# LED.net
KiCad netlist of a schematic drawn in Altium Designer
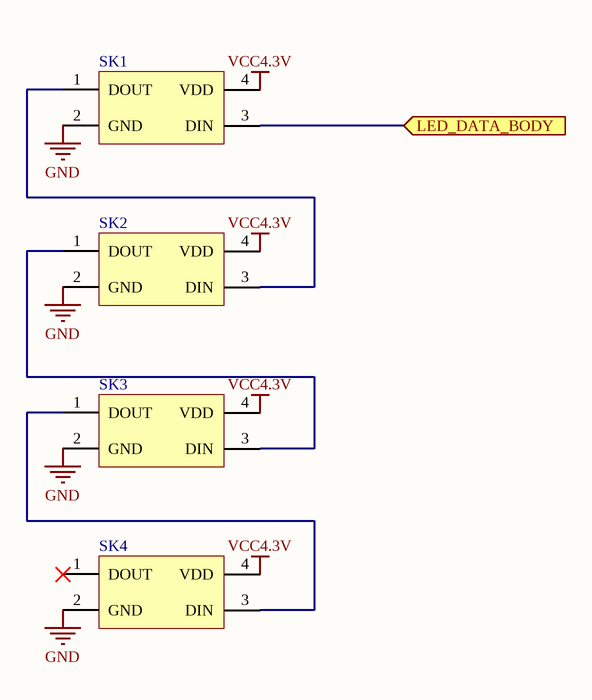
[diagram p0: LED.SchDoc]

(export (version "E")
  (design (tool "Eeschema 10.0.6"))
  (components
    (comp (ref "SK1")
      (value "LED_3535_SK6812")
      (footprint "PCB_ActiveLED:LED_3535_4P")
      (description "LED")
      (libsource (lib "SCH_Active") (part "LED_3535_SK6812"))
    )
    (comp (ref "SK2")
      (value "LED_3535_SK6812")
      (footprint "PCB_ActiveLED:LED_3535_4P")
      (description "LED")
      (libsource (lib "SCH_Active") (part "LED_3535_SK6812"))
    )
    (comp (ref "SK3")
      (value "LED_3535_SK6812")
      (footprint "PCB_ActiveLED:LED_3535_4P")
      (description "LED")
      (libsource (lib "SCH_Active") (part "LED_3535_SK6812"))
    )
    (comp (ref "SK4")
      (value "LED_3535_SK6812")
      (footprint "PCB_ActiveLED:LED_3535_4P")
      (description "LED")
      (libsource (lib "SCH_Active") (part "LED_3535_SK6812"))
    )
  )
  (nets
    (net (code "1") (name "/LED_DATA_BODY") (class "Default")
      (node (ref "SK1") (pin "3") (pinfunction "DIN_3") (pintype "passive"))
    )
    (net (code "2") (name "GND") (class "Default")
      (node (ref "SK1") (pin "2") (pinfunction "GND_2") (pintype "passive"))
      (node (ref "SK2") (pin "2") (pinfunction "GND_2") (pintype "passive"))
      (node (ref "SK3") (pin "2") (pinfunction "GND_2") (pintype "passive"))
      (node (ref "SK4") (pin "2") (pinfunction "GND_2") (pintype "passive"))
    )
    (net (code "3") (name "Net-(SK1-DOUT)") (class "Default")
      (node (ref "SK1") (pin "1") (pinfunction "DOUT_1") (pintype "passive"))
      (node (ref "SK2") (pin "3") (pinfunction "DIN_3") (pintype "passive"))
    )
    (net (code "4") (name "Net-(SK2-DOUT)") (class "Default")
      (node (ref "SK2") (pin "1") (pinfunction "DOUT_1") (pintype "passive"))
      (node (ref "SK3") (pin "3") (pinfunction "DIN_3") (pintype "passive"))
    )
    (net (code "5") (name "Net-(SK3-DOUT)") (class "Default")
      (node (ref "SK3") (pin "1") (pinfunction "DOUT_1") (pintype "passive"))
      (node (ref "SK4") (pin "3") (pinfunction "DIN_3") (pintype "passive"))
    )
    (net (code "6") (name "VCC4.3V") (class "Default")
      (node (ref "SK1") (pin "4") (pinfunction "VDD_4") (pintype "passive"))
      (node (ref "SK2") (pin "4") (pinfunction "VDD_4") (pintype "passive"))
      (node (ref "SK3") (pin "4") (pinfunction "VDD_4") (pintype "passive"))
      (node (ref "SK4") (pin "4") (pinfunction "VDD_4") (pintype "passive"))
    )
    (net (code "7") (name "unconnected-(SK4-DOUT-Pad1)") (class "Default")
      (node (ref "SK4") (pin "1") (pinfunction "DOUT_1") (pintype "passive+no_connect"))
    )
  )
)
